# gms_pcb.net
KiCad netlist of a schematic drawn in EAGLE
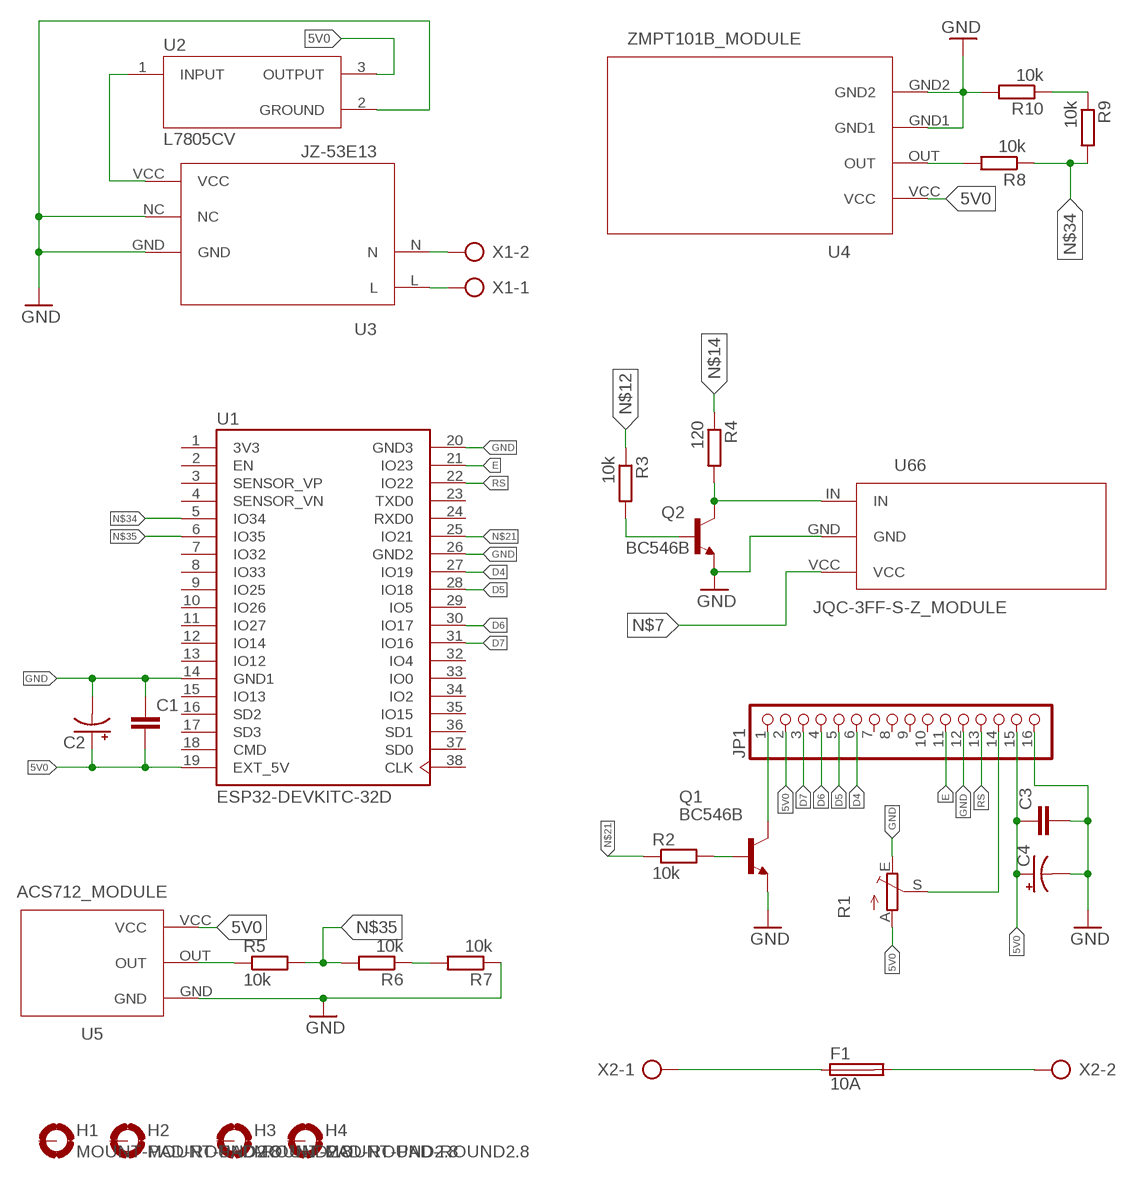
[diagram p0: schematic, sheet 1]

(export (version "E")
  (design (tool "Eeschema 10.0.6"))
  (components
    (comp (ref "C1")
      (value "C-EU025-025X050")
      (footprint "eagle-import:C025-025X050")
      (libsource (lib "eagle-import") (part "C-EU025-025X050"))
    )
    (comp (ref "C2")
      (value "CPOL-USE2.5-6")
      (footprint "eagle-import:E2,5-6")
      (libsource (lib "eagle-import") (part "CPOL-USE2.5-6"))
    )
    (comp (ref "C3")
      (value "C-EU025-025X050")
      (footprint "eagle-import:C025-025X050")
      (libsource (lib "eagle-import") (part "C-EU025-025X050"))
    )
    (comp (ref "C4")
      (value "CPOL-USE2.5-6")
      (footprint "eagle-import:E2,5-6")
      (libsource (lib "eagle-import") (part "CPOL-USE2.5-6"))
    )
    (comp (ref "F1")
      (value "10A")
      (footprint "eagle-import:SH25")
      (fields (field (name "MF") "SCHURTER") (field (name "MPN") "0031.8211"))
      (libsource (lib "eagle-import") (part "SH25"))
    )
    (comp (ref "H1")
      (value "MOUNT-PAD-ROUND2.8")
      (footprint "eagle-import:2,8-PAD")
      (libsource (lib "eagle-import") (part "MOUNT-PAD-ROUND2.8"))
    )
    (comp (ref "H2")
      (value "MOUNT-PAD-ROUND2.8")
      (footprint "eagle-import:2,8-PAD")
      (libsource (lib "eagle-import") (part "MOUNT-PAD-ROUND2.8"))
    )
    (comp (ref "H3")
      (value "MOUNT-PAD-ROUND2.8")
      (footprint "eagle-import:2,8-PAD")
      (libsource (lib "eagle-import") (part "MOUNT-PAD-ROUND2.8"))
    )
    (comp (ref "H4")
      (value "MOUNT-PAD-ROUND2.8")
      (footprint "eagle-import:2,8-PAD")
      (libsource (lib "eagle-import") (part "MOUNT-PAD-ROUND2.8"))
    )
    (comp (ref "JP1")
      (value "PINHD-1X16")
      (footprint "eagle-import:1X16")
      (libsource (lib "eagle-import") (part "PINHD-1X16"))
    )
    (comp (ref "Q1")
      (value "BC546B")
      (footprint "eagle-import:TO92-EBC")
      (libsource (lib "eagle-import") (part "BC546B"))
    )
    (comp (ref "Q2")
      (value "BC546B")
      (footprint "eagle-import:TO92-EBC")
      (libsource (lib "eagle-import") (part "BC546B"))
    )
    (comp (ref "R1")
      (value "TRIM_EU-CA6V")
      (footprint "eagle-import:CA6V")
      (libsource (lib "eagle-import") (part "TRIM_EU-CA6V"))
    )
    (comp (ref "R2")
      (value "10k")
      (footprint "eagle-import:0204_7")
      (libsource (lib "eagle-import") (part "R-EU_0204/7"))
    )
    (comp (ref "R3")
      (value "10k")
      (footprint "eagle-import:0204_7")
      (libsource (lib "eagle-import") (part "R-EU_0204/7"))
    )
    (comp (ref "R4")
      (value "120")
      (footprint "eagle-import:0204_7")
      (libsource (lib "eagle-import") (part "R-EU_0204/7"))
    )
    (comp (ref "R5")
      (value "10k")
      (footprint "eagle-import:0204_7")
      (libsource (lib "eagle-import") (part "R-EU_0204/7"))
    )
    (comp (ref "R6")
      (value "10k")
      (footprint "eagle-import:0204_7")
      (libsource (lib "eagle-import") (part "R-EU_0204/7"))
    )
    (comp (ref "R7")
      (value "10k")
      (footprint "eagle-import:0204_7")
      (libsource (lib "eagle-import") (part "R-EU_0204/7"))
    )
    (comp (ref "R8")
      (value "10k")
      (footprint "eagle-import:0204_7")
      (libsource (lib "eagle-import") (part "R-EU_0204/7"))
    )
    (comp (ref "R9")
      (value "10k")
      (footprint "eagle-import:0204_7")
      (libsource (lib "eagle-import") (part "R-EU_0204/7"))
    )
    (comp (ref "R10")
      (value "10k")
      (footprint "eagle-import:0204_7")
      (libsource (lib "eagle-import") (part "R-EU_0204/7"))
    )
    (comp (ref "U1")
      (value "ESP32-DEVKITC-32D")
      (footprint "eagle-import:MODULE_ESP32-DEVKITC-32D")
      (fields (field (name "MF") "Espressif Systems"))
      (libsource (lib "eagle-import") (part "ESP32-DEVKITC-32D"))
    )
    (comp (ref "U2")
      (value "L7805CV")
      (footprint "eagle-import:TO255P1040X460X1968-3")
      (fields (field (name "MF") "STMicroelectronics"))
      (libsource (lib "eagle-import") (part "L7805CV"))
    )
    (comp (ref "U3")
      (value "JZ-53E13")
      (footprint "eagle-import:JZ-53E13")
      (libsource (lib "eagle-import") (part "JZ-53E13"))
    )
    (comp (ref "U4")
      (value "ZMPT101B_MODULE")
      (footprint "eagle-import:ZMPT101B_MODULE")
      (libsource (lib "eagle-import") (part "ZMPT101B_MODULE"))
    )
    (comp (ref "U5")
      (value "ACS712_MODULE")
      (footprint "eagle-import:ACS712_MODULE")
      (libsource (lib "eagle-import") (part "ACS712_MODULE"))
    )
    (comp (ref "U66")
      (value "JQC-3FF-S-Z_MODULE")
      (footprint "eagle-import:JQC-3FF-S-Z_MOUDLE")
      (libsource (lib "eagle-import") (part "JQC-3FF-S-Z_MODULE"))
    )
    (comp (ref "X1")
      (value "AK500/2")
      (footprint "eagle-import:AK500_2")
      (libsource (lib "eagle-import") (part "AK500/2"))
    )
    (comp (ref "X2")
      (value "AK500/2")
      (footprint "eagle-import:AK500_2")
      (libsource (lib "eagle-import") (part "AK500/2"))
    )
  )
  (nets
    (net (code "1") (name "/3V3") (class "Default")
      (node (ref "U1") (pin "1") (pinfunction "3V3_1") (pintype "power_in"))
    )
    (net (code "2") (name "5V0") (class "Default")
      (node (ref "C1") (pin "2") (pinfunction "2_2") (pintype "passive"))
      (node (ref "C2") (pin "+") (pinfunction "+_+") (pintype "passive"))
      (node (ref "C3") (pin "1") (pinfunction "1_1") (pintype "passive"))
      (node (ref "C4") (pin "+") (pinfunction "+_+") (pintype "passive"))
      (node (ref "JP1") (pin "15") (pinfunction "15_15") (pintype "passive"))
      (node (ref "JP1") (pin "2") (pinfunction "2_2") (pintype "passive"))
      (node (ref "R1") (pin "A") (pinfunction "A_A") (pintype "passive"))
      (node (ref "U1") (pin "19") (pinfunction "EXT_5V_19") (pintype "power_in"))
      (node (ref "U2") (pin "3") (pinfunction "OUTPUT_3") (pintype "output"))
      (node (ref "U4") (pin "VCC") (pinfunction "VCC_VCC") (pintype "bidirectional"))
      (node (ref "U5") (pin "VCC") (pinfunction "VCC_VCC") (pintype "bidirectional"))
    )
    (net (code "3") (name "D4") (class "Default")
      (node (ref "JP1") (pin "6") (pinfunction "6_6") (pintype "passive"))
      (node (ref "U1") (pin "27") (pinfunction "IO19_27") (pintype "bidirectional"))
    )
    (net (code "4") (name "D5") (class "Default")
      (node (ref "JP1") (pin "5") (pinfunction "5_5") (pintype "passive"))
      (node (ref "U1") (pin "28") (pinfunction "IO18_28") (pintype "bidirectional"))
    )
    (net (code "5") (name "D6") (class "Default")
      (node (ref "JP1") (pin "4") (pinfunction "4_4") (pintype "passive"))
      (node (ref "U1") (pin "30") (pinfunction "IO17_30") (pintype "bidirectional"))
    )
    (net (code "6") (name "D7") (class "Default")
      (node (ref "JP1") (pin "3") (pinfunction "3_3") (pintype "passive"))
      (node (ref "U1") (pin "31") (pinfunction "IO16_31") (pintype "bidirectional"))
    )
    (net (code "7") (name "E") (class "Default")
      (node (ref "JP1") (pin "11") (pinfunction "11_11") (pintype "passive"))
      (node (ref "U1") (pin "21") (pinfunction "IO23_21") (pintype "bidirectional"))
    )
    (net (code "8") (name "GND") (class "Default")
      (node (ref "C1") (pin "1") (pinfunction "1_1") (pintype "passive"))
      (node (ref "C2") (pin "-") (pinfunction "-_-") (pintype "passive"))
      (node (ref "C3") (pin "2") (pinfunction "2_2") (pintype "passive"))
      (node (ref "C4") (pin "-") (pinfunction "-_-") (pintype "passive"))
      (node (ref "JP1") (pin "12") (pinfunction "12_12") (pintype "passive"))
      (node (ref "JP1") (pin "16") (pinfunction "16_16") (pintype "passive"))
      (node (ref "Q1") (pin "E") (pinfunction "E_E") (pintype "passive"))
      (node (ref "Q2") (pin "E") (pinfunction "E_E") (pintype "passive"))
      (node (ref "R1") (pin "E") (pinfunction "E_E") (pintype "passive"))
      (node (ref "R10") (pin "2") (pinfunction "2_2") (pintype "passive"))
      (node (ref "R7") (pin "1") (pinfunction "1_1") (pintype "passive"))
      (node (ref "U1") (pin "14") (pinfunction "GND1_14") (pintype "power_in"))
      (node (ref "U1") (pin "20") (pinfunction "GND3_20") (pintype "power_in"))
      (node (ref "U1") (pin "26") (pinfunction "GND2_26") (pintype "power_in"))
      (node (ref "U2") (pin "2") (pinfunction "GROUND_2") (pintype "power_in"))
      (node (ref "U3") (pin "GND") (pinfunction "GND_GND") (pintype "bidirectional"))
      (node (ref "U3") (pin "NC") (pinfunction "NC_NC") (pintype "bidirectional"))
      (node (ref "U4") (pin "GND1") (pinfunction "GND1_GND1") (pintype "bidirectional"))
      (node (ref "U4") (pin "GND2") (pinfunction "GND2_GND2") (pintype "bidirectional"))
      (node (ref "U5") (pin "GND") (pinfunction "GND_GND") (pintype "bidirectional"))
      (node (ref "U66") (pin "GND") (pinfunction "GND_GND") (pintype "bidirectional"))
    )
    (net (code "9") (name "N$7") (class "Default")
      (node (ref "U66") (pin "VCC") (pinfunction "VCC_VCC") (pintype "bidirectional"))
    )
    (net (code "10") (name "N$12") (class "Default")
      (node (ref "R3") (pin "1") (pinfunction "1_1") (pintype "passive"))
    )
    (net (code "11") (name "N$14") (class "Default")
      (node (ref "R4") (pin "1") (pinfunction "1_1") (pintype "passive"))
    )
    (net (code "12") (name "N$21") (class "Default")
      (node (ref "R2") (pin "1") (pinfunction "1_1") (pintype "passive"))
      (node (ref "U1") (pin "25") (pinfunction "IO21_25") (pintype "bidirectional"))
    )
    (net (code "13") (name "N$34") (class "Default")
      (node (ref "R8") (pin "1") (pinfunction "1_1") (pintype "passive"))
      (node (ref "R9") (pin "2") (pinfunction "2_2") (pintype "passive"))
      (node (ref "U1") (pin "5") (pinfunction "IO34_5") (pintype "bidirectional"))
    )
    (net (code "14") (name "N$35") (class "Default")
      (node (ref "R5") (pin "2") (pinfunction "2_2") (pintype "passive"))
      (node (ref "R6") (pin "2") (pinfunction "2_2") (pintype "passive"))
      (node (ref "U1") (pin "6") (pinfunction "IO35_6") (pintype "bidirectional"))
    )
    (net (code "15") (name "Net-(JP1-Pad1)") (class "Default")
      (node (ref "JP1") (pin "1") (pinfunction "1_1") (pintype "passive"))
      (node (ref "Q1") (pin "C") (pinfunction "C_C") (pintype "passive"))
    )
    (net (code "16") (name "Net-(JP1-Pad14)") (class "Default")
      (node (ref "JP1") (pin "14") (pinfunction "14_14") (pintype "passive"))
      (node (ref "R1") (pin "S") (pinfunction "S_S") (pintype "passive"))
    )
    (net (code "17") (name "Net-(Q1-PadB)") (class "Default")
      (node (ref "Q1") (pin "B") (pinfunction "B_B") (pintype "passive"))
      (node (ref "R2") (pin "2") (pinfunction "2_2") (pintype "passive"))
    )
    (net (code "18") (name "Net-(Q2-PadB)") (class "Default")
      (node (ref "Q2") (pin "B") (pinfunction "B_B") (pintype "passive"))
      (node (ref "R3") (pin "2") (pinfunction "2_2") (pintype "passive"))
    )
    (net (code "19") (name "Net-(Q2-PadC)") (class "Default")
      (node (ref "Q2") (pin "C") (pinfunction "C_C") (pintype "passive"))
      (node (ref "R4") (pin "2") (pinfunction "2_2") (pintype "passive"))
      (node (ref "U66") (pin "IN") (pinfunction "IN_IN") (pintype "bidirectional"))
    )
    (net (code "20") (name "Net-(R5-Pad1)") (class "Default")
      (node (ref "R5") (pin "1") (pinfunction "1_1") (pintype "passive"))
      (node (ref "U5") (pin "OUT") (pinfunction "OUT_OUT") (pintype "bidirectional"))
    )
    (net (code "21") (name "Net-(R6-Pad1)") (class "Default")
      (node (ref "R6") (pin "1") (pinfunction "1_1") (pintype "passive"))
      (node (ref "R7") (pin "2") (pinfunction "2_2") (pintype "passive"))
    )
    (net (code "22") (name "Net-(R8-Pad2)") (class "Default")
      (node (ref "R8") (pin "2") (pinfunction "2_2") (pintype "passive"))
      (node (ref "U4") (pin "OUT") (pinfunction "OUT_OUT") (pintype "bidirectional"))
    )
    (net (code "23") (name "Net-(R10-Pad1)") (class "Default")
      (node (ref "R10") (pin "1") (pinfunction "1_1") (pintype "passive"))
      (node (ref "R9") (pin "1") (pinfunction "1_1") (pintype "passive"))
    )
    (net (code "24") (name "Net-(U2-INPUT)") (class "Default")
      (node (ref "U2") (pin "1") (pinfunction "INPUT_1") (pintype "input"))
      (node (ref "U3") (pin "VCC") (pinfunction "VCC_VCC") (pintype "bidirectional"))
    )
    (net (code "25") (name "Net-(X1A-KL)") (class "Default")
      (node (ref "U3") (pin "L") (pinfunction "L_L") (pintype "bidirectional"))
      (node (ref "X1") (pin "1") (pinfunction "KL_1") (pintype "passive"))
    )
    (net (code "26") (name "Net-(X1B-KL)") (class "Default")
      (node (ref "U3") (pin "N") (pinfunction "N_N") (pintype "bidirectional"))
      (node (ref "X1") (pin "2") (pinfunction "KL_2") (pintype "passive"))
    )
    (net (code "27") (name "Net-(X2A-KL)") (class "Default")
      (node (ref "F1") (pin "1") (pinfunction "1_1") (pintype "passive"))
      (node (ref "X2") (pin "1") (pinfunction "KL_1") (pintype "passive"))
    )
    (net (code "28") (name "Net-(X2B-KL)") (class "Default")
      (node (ref "F1") (pin "2") (pinfunction "2_2") (pintype "passive"))
      (node (ref "X2") (pin "2") (pinfunction "KL_2") (pintype "passive"))
    )
    (net (code "29") (name "RS") (class "Default")
      (node (ref "JP1") (pin "13") (pinfunction "13_13") (pintype "passive"))
      (node (ref "U1") (pin "22") (pinfunction "IO22_22") (pintype "bidirectional"))
    )
    (net (code "30") (name "unconnected-(H1-MOUNT-PadB2,8)") (class "Default")
      (node (ref "H1") (pin "B2,8") (pinfunction "MOUNT_B2,8") (pintype "passive"))
    )
    (net (code "31") (name "unconnected-(H2-MOUNT-PadB2,8)") (class "Default")
      (node (ref "H2") (pin "B2,8") (pinfunction "MOUNT_B2,8") (pintype "passive"))
    )
    (net (code "32") (name "unconnected-(H3-MOUNT-PadB2,8)") (class "Default")
      (node (ref "H3") (pin "B2,8") (pinfunction "MOUNT_B2,8") (pintype "passive"))
    )
    (net (code "33") (name "unconnected-(H4-MOUNT-PadB2,8)") (class "Default")
      (node (ref "H4") (pin "B2,8") (pinfunction "MOUNT_B2,8") (pintype "passive"))
    )
    (net (code "34") (name "unconnected-(JP1-Pad7)") (class "Default")
      (node (ref "JP1") (pin "7") (pinfunction "7_7") (pintype "passive"))
    )
    (net (code "35") (name "unconnected-(JP1-Pad8)") (class "Default")
      (node (ref "JP1") (pin "8") (pinfunction "8_8") (pintype "passive"))
    )
    (net (code "36") (name "unconnected-(JP1-Pad9)") (class "Default")
      (node (ref "JP1") (pin "9") (pinfunction "9_9") (pintype "passive"))
    )
    (net (code "37") (name "unconnected-(JP1-Pad10)") (class "Default")
      (node (ref "JP1") (pin "10") (pinfunction "10_10") (pintype "passive"))
    )
    (net (code "38") (name "unconnected-(U1-CLK-Pad38)") (class "Default")
      (node (ref "U1") (pin "38") (pinfunction "CLK_38") (pintype "input"))
    )
    (net (code "39") (name "unconnected-(U1-CMD-Pad18)") (class "Default")
      (node (ref "U1") (pin "18") (pinfunction "CMD_18") (pintype "bidirectional"))
    )
    (net (code "40") (name "unconnected-(U1-EN-Pad2)") (class "Default")
      (node (ref "U1") (pin "2") (pinfunction "EN_2") (pintype "input"))
    )
    (net (code "41") (name "unconnected-(U1-IO0-Pad33)") (class "Default")
      (node (ref "U1") (pin "33") (pinfunction "IO0_33") (pintype "bidirectional"))
    )
    (net (code "42") (name "unconnected-(U1-IO2-Pad34)") (class "Default")
      (node (ref "U1") (pin "34") (pinfunction "IO2_34") (pintype "bidirectional"))
    )
    (net (code "43") (name "unconnected-(U1-IO4-Pad32)") (class "Default")
      (node (ref "U1") (pin "32") (pinfunction "IO4_32") (pintype "bidirectional"))
    )
    (net (code "44") (name "unconnected-(U1-IO5-Pad29)") (class "Default")
      (node (ref "U1") (pin "29") (pinfunction "IO5_29") (pintype "bidirectional"))
    )
    (net (code "45") (name "unconnected-(U1-IO12-Pad13)") (class "Default")
      (node (ref "U1") (pin "13") (pinfunction "IO12_13") (pintype "bidirectional"))
    )
    (net (code "46") (name "unconnected-(U1-IO13-Pad15)") (class "Default")
      (node (ref "U1") (pin "15") (pinfunction "IO13_15") (pintype "bidirectional"))
    )
    (net (code "47") (name "unconnected-(U1-IO14-Pad12)") (class "Default")
      (node (ref "U1") (pin "12") (pinfunction "IO14_12") (pintype "bidirectional"))
    )
    (net (code "48") (name "unconnected-(U1-IO15-Pad35)") (class "Default")
      (node (ref "U1") (pin "35") (pinfunction "IO15_35") (pintype "bidirectional"))
    )
    (net (code "49") (name "unconnected-(U1-IO25-Pad9)") (class "Default")
      (node (ref "U1") (pin "9") (pinfunction "IO25_9") (pintype "bidirectional"))
    )
    (net (code "50") (name "unconnected-(U1-IO26-Pad10)") (class "Default")
      (node (ref "U1") (pin "10") (pinfunction "IO26_10") (pintype "bidirectional"))
    )
    (net (code "51") (name "unconnected-(U1-IO27-Pad11)") (class "Default")
      (node (ref "U1") (pin "11") (pinfunction "IO27_11") (pintype "bidirectional"))
    )
    (net (code "52") (name "unconnected-(U1-IO32-Pad7)") (class "Default")
      (node (ref "U1") (pin "7") (pinfunction "IO32_7") (pintype "bidirectional"))
    )
    (net (code "53") (name "unconnected-(U1-IO33-Pad8)") (class "Default")
      (node (ref "U1") (pin "8") (pinfunction "IO33_8") (pintype "bidirectional"))
    )
    (net (code "54") (name "unconnected-(U1-RXD0-Pad24)") (class "Default")
      (node (ref "U1") (pin "24") (pinfunction "RXD0_24") (pintype "input"))
    )
    (net (code "55") (name "unconnected-(U1-SD0-Pad37)") (class "Default")
      (node (ref "U1") (pin "37") (pinfunction "SD0_37") (pintype "bidirectional"))
    )
    (net (code "56") (name "unconnected-(U1-SD1-Pad36)") (class "Default")
      (node (ref "U1") (pin "36") (pinfunction "SD1_36") (pintype "bidirectional"))
    )
    (net (code "57") (name "unconnected-(U1-SD2-Pad16)") (class "Default")
      (node (ref "U1") (pin "16") (pinfunction "SD2_16") (pintype "bidirectional"))
    )
    (net (code "58") (name "unconnected-(U1-SD3-Pad17)") (class "Default")
      (node (ref "U1") (pin "17") (pinfunction "SD3_17") (pintype "bidirectional"))
    )
    (net (code "59") (name "unconnected-(U1-SENSOR_VN-Pad4)") (class "Default")
      (node (ref "U1") (pin "4") (pinfunction "SENSOR_VN_4") (pintype "input"))
    )
    (net (code "60") (name "unconnected-(U1-SENSOR_VP-Pad3)") (class "Default")
      (node (ref "U1") (pin "3") (pinfunction "SENSOR_VP_3") (pintype "input"))
    )
    (net (code "61") (name "unconnected-(U1-TXD0-Pad23)") (class "Default")
      (node (ref "U1") (pin "23") (pinfunction "TXD0_23") (pintype "output"))
    )
  )
)
